# BD0006.net
KiCad netlist of a schematic drawn in EAGLE
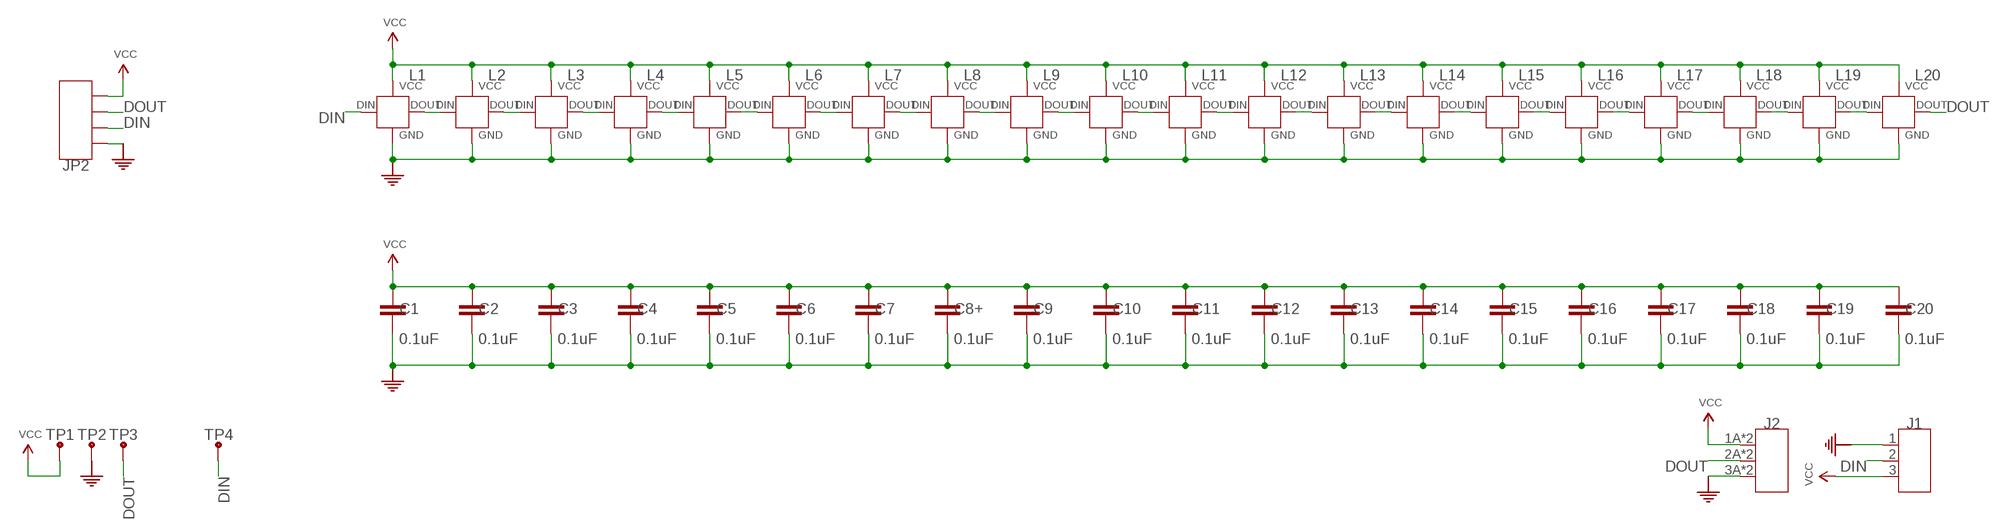
[diagram p0: schematic, sheet 1]

(export (version "E")
  (design (tool "Eeschema 10.0.6"))
  (components
    (comp (ref "C1")
      (value "0.1uF")
      (footprint "eagle-import:0402")
      (libsource (lib "eagle-import") (part "CAPACITOR-0402"))
    )
    (comp (ref "C2")
      (value "0.1uF")
      (footprint "eagle-import:0402")
      (libsource (lib "eagle-import") (part "CAPACITOR-0402"))
    )
    (comp (ref "C3")
      (value "0.1uF")
      (footprint "eagle-import:0402")
      (libsource (lib "eagle-import") (part "CAPACITOR-0402"))
    )
    (comp (ref "C4")
      (value "0.1uF")
      (footprint "eagle-import:0402")
      (libsource (lib "eagle-import") (part "CAPACITOR-0402"))
    )
    (comp (ref "C5")
      (value "0.1uF")
      (footprint "eagle-import:0402")
      (libsource (lib "eagle-import") (part "CAPACITOR-0402"))
    )
    (comp (ref "C6")
      (value "0.1uF")
      (footprint "eagle-import:0402")
      (libsource (lib "eagle-import") (part "CAPACITOR-0402"))
    )
    (comp (ref "C7")
      (value "0.1uF")
      (footprint "eagle-import:0402")
      (libsource (lib "eagle-import") (part "CAPACITOR-0402"))
    )
    (comp (ref "C8+")
      (value "0.1uF")
      (footprint "eagle-import:0402")
      (libsource (lib "eagle-import") (part "CAPACITOR-0402"))
    )
    (comp (ref "C9")
      (value "0.1uF")
      (footprint "eagle-import:0402")
      (libsource (lib "eagle-import") (part "CAPACITOR-0402"))
    )
    (comp (ref "C10")
      (value "0.1uF")
      (footprint "eagle-import:0402")
      (libsource (lib "eagle-import") (part "CAPACITOR-0402"))
    )
    (comp (ref "C11")
      (value "0.1uF")
      (footprint "eagle-import:0402")
      (libsource (lib "eagle-import") (part "CAPACITOR-0402"))
    )
    (comp (ref "C12")
      (value "0.1uF")
      (footprint "eagle-import:0402")
      (libsource (lib "eagle-import") (part "CAPACITOR-0402"))
    )
    (comp (ref "C13")
      (value "0.1uF")
      (footprint "eagle-import:0402")
      (libsource (lib "eagle-import") (part "CAPACITOR-0402"))
    )
    (comp (ref "C14")
      (value "0.1uF")
      (footprint "eagle-import:0402")
      (libsource (lib "eagle-import") (part "CAPACITOR-0402"))
    )
    (comp (ref "C15")
      (value "0.1uF")
      (footprint "eagle-import:0402")
      (libsource (lib "eagle-import") (part "CAPACITOR-0402"))
    )
    (comp (ref "C16")
      (value "0.1uF")
      (footprint "eagle-import:0402")
      (libsource (lib "eagle-import") (part "CAPACITOR-0402"))
    )
    (comp (ref "C17")
      (value "0.1uF")
      (footprint "eagle-import:0402")
      (libsource (lib "eagle-import") (part "CAPACITOR-0402"))
    )
    (comp (ref "C18")
      (value "0.1uF")
      (footprint "eagle-import:0402")
      (libsource (lib "eagle-import") (part "CAPACITOR-0402"))
    )
    (comp (ref "C19")
      (value "0.1uF")
      (footprint "eagle-import:0402")
      (libsource (lib "eagle-import") (part "CAPACITOR-0402"))
    )
    (comp (ref "C20")
      (value "0.1uF")
      (footprint "eagle-import:0402")
      (libsource (lib "eagle-import") (part "CAPACITOR-0402"))
    )
    (comp (ref "J1")
      (value "HEADER_1X3MALE")
      (footprint "eagle-import:M3SMD_RIGHTANGLE")
      (libsource (lib "eagle-import") (part "HEADER_1X3MALE"))
    )
    (comp (ref "J2")
      (value "HEADER_1X3FEMALE")
      (footprint "eagle-import:F3SMD_RIGHTANGLE")
      (libsource (lib "eagle-import") (part "HEADER_1X3FEMALE"))
    )
    (comp (ref "JP2")
      (value "HEADER_1X4")
      (footprint "eagle-import:1X04-CLEANBIG")
      (libsource (lib "eagle-import") (part "HEADER_1X4"))
    )
    (comp (ref "L1")
      (value "WS2812B-B")
      (footprint "eagle-import:SK6812-B")
      (libsource (lib "eagle-import") (part "WS2812B-B"))
    )
    (comp (ref "L2")
      (value "WS2812B-B")
      (footprint "eagle-import:SK6812-B")
      (libsource (lib "eagle-import") (part "WS2812B-B"))
    )
    (comp (ref "L3")
      (value "WS2812B-B")
      (footprint "eagle-import:SK6812-B")
      (libsource (lib "eagle-import") (part "WS2812B-B"))
    )
    (comp (ref "L4")
      (value "WS2812B-B")
      (footprint "eagle-import:SK6812-B")
      (libsource (lib "eagle-import") (part "WS2812B-B"))
    )
    (comp (ref "L5")
      (value "WS2812B-B")
      (footprint "eagle-import:SK6812-B")
      (libsource (lib "eagle-import") (part "WS2812B-B"))
    )
    (comp (ref "L6")
      (value "WS2812B-B")
      (footprint "eagle-import:SK6812-B")
      (libsource (lib "eagle-import") (part "WS2812B-B"))
    )
    (comp (ref "L7")
      (value "WS2812B-B")
      (footprint "eagle-import:SK6812-B")
      (libsource (lib "eagle-import") (part "WS2812B-B"))
    )
    (comp (ref "L8")
      (value "WS2812B-B")
      (footprint "eagle-import:SK6812-B")
      (libsource (lib "eagle-import") (part "WS2812B-B"))
    )
    (comp (ref "L9")
      (value "WS2812B-B")
      (footprint "eagle-import:SK6812-B")
      (libsource (lib "eagle-import") (part "WS2812B-B"))
    )
    (comp (ref "L10")
      (value "WS2812B-B")
      (footprint "eagle-import:SK6812-B")
      (libsource (lib "eagle-import") (part "WS2812B-B"))
    )
    (comp (ref "L11")
      (value "WS2812B-B")
      (footprint "eagle-import:SK6812-B")
      (libsource (lib "eagle-import") (part "WS2812B-B"))
    )
    (comp (ref "L12")
      (value "WS2812B-B")
      (footprint "eagle-import:SK6812-B")
      (libsource (lib "eagle-import") (part "WS2812B-B"))
    )
    (comp (ref "L13")
      (value "WS2812B-B")
      (footprint "eagle-import:SK6812-B")
      (libsource (lib "eagle-import") (part "WS2812B-B"))
    )
    (comp (ref "L14")
      (value "WS2812B-B")
      (footprint "eagle-import:SK6812-B")
      (libsource (lib "eagle-import") (part "WS2812B-B"))
    )
    (comp (ref "L15")
      (value "WS2812B-B")
      (footprint "eagle-import:SK6812-B")
      (libsource (lib "eagle-import") (part "WS2812B-B"))
    )
    (comp (ref "L16")
      (value "WS2812B-B")
      (footprint "eagle-import:SK6812-B")
      (libsource (lib "eagle-import") (part "WS2812B-B"))
    )
    (comp (ref "L17")
      (value "WS2812B-B")
      (footprint "eagle-import:SK6812-B")
      (libsource (lib "eagle-import") (part "WS2812B-B"))
    )
    (comp (ref "L18")
      (value "WS2812B-B")
      (footprint "eagle-import:SK6812-B")
      (libsource (lib "eagle-import") (part "WS2812B-B"))
    )
    (comp (ref "L19")
      (value "WS2812B-B")
      (footprint "eagle-import:SK6812-B")
      (libsource (lib "eagle-import") (part "WS2812B-B"))
    )
    (comp (ref "L20")
      (value "WS2812B-B")
      (footprint "eagle-import:SK6812-B")
      (libsource (lib "eagle-import") (part "WS2812B-B"))
    )
    (comp (ref "TP1")
      (value "VCC")
      (footprint "eagle-import:TEST_POINT")
      (libsource (lib "eagle-import") (part "TEST_POINT"))
    )
    (comp (ref "TP2")
      (value "GND")
      (footprint "eagle-import:TEST_POINT")
      (libsource (lib "eagle-import") (part "TEST_POINT"))
    )
    (comp (ref "TP3")
      (value "DOUT")
      (footprint "eagle-import:TEST_POINT")
      (libsource (lib "eagle-import") (part "TEST_POINT"))
    )
    (comp (ref "TP4")
      (value "DIN")
      (footprint "eagle-import:TEST_POINT")
      (libsource (lib "eagle-import") (part "TEST_POINT"))
    )
  )
  (nets
    (net (code "1") (name "/DIN") (class "Default")
      (node (ref "J1") (pin "2") (pinfunction "P$2_2") (pintype "bidirectional"))
      (node (ref "JP2") (pin "2") (pinfunction "P$2_2") (pintype "bidirectional"))
      (node (ref "L1") (pin "2") (pinfunction "DIN_2") (pintype "bidirectional"))
      (node (ref "TP4") (pin "P$1") (pinfunction "P$1_P$1") (pintype "input"))
    )
    (net (code "2") (name "/DOUT") (class "Default")
      (node (ref "J2") (pin "2A") (pinfunction "P$2_2A") (pintype "bidirectional"))
      (node (ref "J2") (pin "2B") (pinfunction "P$2_2B") (pintype "bidirectional"))
      (node (ref "JP2") (pin "3") (pinfunction "P$3_3") (pintype "bidirectional"))
      (node (ref "L20") (pin "4") (pinfunction "DOUT_4") (pintype "bidirectional"))
      (node (ref "TP3") (pin "P$1") (pinfunction "P$1_P$1") (pintype "input"))
    )
    (net (code "3") (name "GND") (class "Default")
      (node (ref "C1") (pin "P$2") (pinfunction "2_P$2") (pintype "passive"))
      (node (ref "C10") (pin "P$2") (pinfunction "2_P$2") (pintype "passive"))
      (node (ref "C11") (pin "P$2") (pinfunction "2_P$2") (pintype "passive"))
      (node (ref "C12") (pin "P$2") (pinfunction "2_P$2") (pintype "passive"))
      (node (ref "C13") (pin "P$2") (pinfunction "2_P$2") (pintype "passive"))
      (node (ref "C14") (pin "P$2") (pinfunction "2_P$2") (pintype "passive"))
      (node (ref "C15") (pin "P$2") (pinfunction "2_P$2") (pintype "passive"))
      (node (ref "C16") (pin "P$2") (pinfunction "2_P$2") (pintype "passive"))
      (node (ref "C17") (pin "P$2") (pinfunction "2_P$2") (pintype "passive"))
      (node (ref "C18") (pin "P$2") (pinfunction "2_P$2") (pintype "passive"))
      (node (ref "C19") (pin "P$2") (pinfunction "2_P$2") (pintype "passive"))
      (node (ref "C2") (pin "P$2") (pinfunction "2_P$2") (pintype "passive"))
      (node (ref "C20") (pin "P$2") (pinfunction "2_P$2") (pintype "passive"))
      (node (ref "C3") (pin "P$2") (pinfunction "2_P$2") (pintype "passive"))
      (node (ref "C4") (pin "P$2") (pinfunction "2_P$2") (pintype "passive"))
      (node (ref "C5") (pin "P$2") (pinfunction "2_P$2") (pintype "passive"))
      (node (ref "C6") (pin "P$2") (pinfunction "2_P$2") (pintype "passive"))
      (node (ref "C7") (pin "P$2") (pinfunction "2_P$2") (pintype "passive"))
      (node (ref "C8+") (pin "P$2") (pinfunction "2_P$2") (pintype "passive"))
      (node (ref "C9") (pin "P$2") (pinfunction "2_P$2") (pintype "passive"))
      (node (ref "J1") (pin "1") (pinfunction "P$1_1") (pintype "bidirectional"))
      (node (ref "J2") (pin "3A") (pinfunction "P$3_3A") (pintype "bidirectional"))
      (node (ref "J2") (pin "3B") (pinfunction "P$3_3B") (pintype "bidirectional"))
      (node (ref "JP2") (pin "1") (pinfunction "P$1_1") (pintype "bidirectional"))
      (node (ref "L1") (pin "1") (pinfunction "VSS_1") (pintype "bidirectional"))
      (node (ref "L10") (pin "1") (pinfunction "VSS_1") (pintype "bidirectional"))
      (node (ref "L11") (pin "1") (pinfunction "VSS_1") (pintype "bidirectional"))
      (node (ref "L12") (pin "1") (pinfunction "VSS_1") (pintype "bidirectional"))
      (node (ref "L13") (pin "1") (pinfunction "VSS_1") (pintype "bidirectional"))
      (node (ref "L14") (pin "1") (pinfunction "VSS_1") (pintype "bidirectional"))
      (node (ref "L15") (pin "1") (pinfunction "VSS_1") (pintype "bidirectional"))
      (node (ref "L16") (pin "1") (pinfunction "VSS_1") (pintype "bidirectional"))
      (node (ref "L17") (pin "1") (pinfunction "VSS_1") (pintype "bidirectional"))
      (node (ref "L18") (pin "1") (pinfunction "VSS_1") (pintype "bidirectional"))
      (node (ref "L19") (pin "1") (pinfunction "VSS_1") (pintype "bidirectional"))
      (node (ref "L2") (pin "1") (pinfunction "VSS_1") (pintype "bidirectional"))
      (node (ref "L20") (pin "1") (pinfunction "VSS_1") (pintype "bidirectional"))
      (node (ref "L3") (pin "1") (pinfunction "VSS_1") (pintype "bidirectional"))
      (node (ref "L4") (pin "1") (pinfunction "VSS_1") (pintype "bidirectional"))
      (node (ref "L5") (pin "1") (pinfunction "VSS_1") (pintype "bidirectional"))
      (node (ref "L6") (pin "1") (pinfunction "VSS_1") (pintype "bidirectional"))
      (node (ref "L7") (pin "1") (pinfunction "VSS_1") (pintype "bidirectional"))
      (node (ref "L8") (pin "1") (pinfunction "VSS_1") (pintype "bidirectional"))
      (node (ref "L9") (pin "1") (pinfunction "VSS_1") (pintype "bidirectional"))
      (node (ref "TP2") (pin "P$1") (pinfunction "P$1_P$1") (pintype "input"))
    )
    (net (code "4") (name "Net-(L1-DOUT)") (class "Default")
      (node (ref "L1") (pin "4") (pinfunction "DOUT_4") (pintype "bidirectional"))
      (node (ref "L2") (pin "2") (pinfunction "DIN_2") (pintype "bidirectional"))
    )
    (net (code "5") (name "Net-(L2-DOUT)") (class "Default")
      (node (ref "L2") (pin "4") (pinfunction "DOUT_4") (pintype "bidirectional"))
      (node (ref "L3") (pin "2") (pinfunction "DIN_2") (pintype "bidirectional"))
    )
    (net (code "6") (name "Net-(L3-DOUT)") (class "Default")
      (node (ref "L3") (pin "4") (pinfunction "DOUT_4") (pintype "bidirectional"))
      (node (ref "L4") (pin "2") (pinfunction "DIN_2") (pintype "bidirectional"))
    )
    (net (code "7") (name "Net-(L4-DOUT)") (class "Default")
      (node (ref "L4") (pin "4") (pinfunction "DOUT_4") (pintype "bidirectional"))
      (node (ref "L5") (pin "2") (pinfunction "DIN_2") (pintype "bidirectional"))
    )
    (net (code "8") (name "Net-(L5-DOUT)") (class "Default")
      (node (ref "L5") (pin "4") (pinfunction "DOUT_4") (pintype "bidirectional"))
      (node (ref "L6") (pin "2") (pinfunction "DIN_2") (pintype "bidirectional"))
    )
    (net (code "9") (name "Net-(L6-DOUT)") (class "Default")
      (node (ref "L6") (pin "4") (pinfunction "DOUT_4") (pintype "bidirectional"))
      (node (ref "L7") (pin "2") (pinfunction "DIN_2") (pintype "bidirectional"))
    )
    (net (code "10") (name "Net-(L7-DOUT)") (class "Default")
      (node (ref "L7") (pin "4") (pinfunction "DOUT_4") (pintype "bidirectional"))
      (node (ref "L8") (pin "2") (pinfunction "DIN_2") (pintype "bidirectional"))
    )
    (net (code "11") (name "Net-(L8-DOUT)") (class "Default")
      (node (ref "L8") (pin "4") (pinfunction "DOUT_4") (pintype "bidirectional"))
      (node (ref "L9") (pin "2") (pinfunction "DIN_2") (pintype "bidirectional"))
    )
    (net (code "12") (name "Net-(L10-DIN)") (class "Default")
      (node (ref "L10") (pin "2") (pinfunction "DIN_2") (pintype "bidirectional"))
      (node (ref "L9") (pin "4") (pinfunction "DOUT_4") (pintype "bidirectional"))
    )
    (net (code "13") (name "Net-(L10-DOUT)") (class "Default")
      (node (ref "L10") (pin "4") (pinfunction "DOUT_4") (pintype "bidirectional"))
      (node (ref "L11") (pin "2") (pinfunction "DIN_2") (pintype "bidirectional"))
    )
    (net (code "14") (name "Net-(L11-DOUT)") (class "Default")
      (node (ref "L11") (pin "4") (pinfunction "DOUT_4") (pintype "bidirectional"))
      (node (ref "L12") (pin "2") (pinfunction "DIN_2") (pintype "bidirectional"))
    )
    (net (code "15") (name "Net-(L12-DOUT)") (class "Default")
      (node (ref "L12") (pin "4") (pinfunction "DOUT_4") (pintype "bidirectional"))
      (node (ref "L13") (pin "2") (pinfunction "DIN_2") (pintype "bidirectional"))
    )
    (net (code "16") (name "Net-(L13-DOUT)") (class "Default")
      (node (ref "L13") (pin "4") (pinfunction "DOUT_4") (pintype "bidirectional"))
      (node (ref "L14") (pin "2") (pinfunction "DIN_2") (pintype "bidirectional"))
    )
    (net (code "17") (name "Net-(L14-DOUT)") (class "Default")
      (node (ref "L14") (pin "4") (pinfunction "DOUT_4") (pintype "bidirectional"))
      (node (ref "L15") (pin "2") (pinfunction "DIN_2") (pintype "bidirectional"))
    )
    (net (code "18") (name "Net-(L15-DOUT)") (class "Default")
      (node (ref "L15") (pin "4") (pinfunction "DOUT_4") (pintype "bidirectional"))
      (node (ref "L16") (pin "2") (pinfunction "DIN_2") (pintype "bidirectional"))
    )
    (net (code "19") (name "Net-(L16-DOUT)") (class "Default")
      (node (ref "L16") (pin "4") (pinfunction "DOUT_4") (pintype "bidirectional"))
      (node (ref "L17") (pin "2") (pinfunction "DIN_2") (pintype "bidirectional"))
    )
    (net (code "20") (name "Net-(L17-DOUT)") (class "Default")
      (node (ref "L17") (pin "4") (pinfunction "DOUT_4") (pintype "bidirectional"))
      (node (ref "L18") (pin "2") (pinfunction "DIN_2") (pintype "bidirectional"))
    )
    (net (code "21") (name "Net-(L18-DOUT)") (class "Default")
      (node (ref "L18") (pin "4") (pinfunction "DOUT_4") (pintype "bidirectional"))
      (node (ref "L19") (pin "2") (pinfunction "DIN_2") (pintype "bidirectional"))
    )
    (net (code "22") (name "Net-(L19-DOUT)") (class "Default")
      (node (ref "L19") (pin "4") (pinfunction "DOUT_4") (pintype "bidirectional"))
      (node (ref "L20") (pin "2") (pinfunction "DIN_2") (pintype "bidirectional"))
    )
    (net (code "23") (name "VCC") (class "Default")
      (node (ref "C1") (pin "P$1") (pinfunction "1_P$1") (pintype "passive"))
      (node (ref "C10") (pin "P$1") (pinfunction "1_P$1") (pintype "passive"))
      (node (ref "C11") (pin "P$1") (pinfunction "1_P$1") (pintype "passive"))
      (node (ref "C12") (pin "P$1") (pinfunction "1_P$1") (pintype "passive"))
      (node (ref "C13") (pin "P$1") (pinfunction "1_P$1") (pintype "passive"))
      (node (ref "C14") (pin "P$1") (pinfunction "1_P$1") (pintype "passive"))
      (node (ref "C15") (pin "P$1") (pinfunction "1_P$1") (pintype "passive"))
      (node (ref "C16") (pin "P$1") (pinfunction "1_P$1") (pintype "passive"))
      (node (ref "C17") (pin "P$1") (pinfunction "1_P$1") (pintype "passive"))
      (node (ref "C18") (pin "P$1") (pinfunction "1_P$1") (pintype "passive"))
      (node (ref "C19") (pin "P$1") (pinfunction "1_P$1") (pintype "passive"))
      (node (ref "C2") (pin "P$1") (pinfunction "1_P$1") (pintype "passive"))
      (node (ref "C20") (pin "P$1") (pinfunction "1_P$1") (pintype "passive"))
      (node (ref "C3") (pin "P$1") (pinfunction "1_P$1") (pintype "passive"))
      (node (ref "C4") (pin "P$1") (pinfunction "1_P$1") (pintype "passive"))
      (node (ref "C5") (pin "P$1") (pinfunction "1_P$1") (pintype "passive"))
      (node (ref "C6") (pin "P$1") (pinfunction "1_P$1") (pintype "passive"))
      (node (ref "C7") (pin "P$1") (pinfunction "1_P$1") (pintype "passive"))
      (node (ref "C8+") (pin "P$1") (pinfunction "1_P$1") (pintype "passive"))
      (node (ref "C9") (pin "P$1") (pinfunction "1_P$1") (pintype "passive"))
      (node (ref "J1") (pin "3") (pinfunction "P$3_3") (pintype "bidirectional"))
      (node (ref "J2") (pin "1A") (pinfunction "P$1_1A") (pintype "bidirectional"))
      (node (ref "J2") (pin "1B") (pinfunction "P$1_1B") (pintype "bidirectional"))
      (node (ref "JP2") (pin "4") (pinfunction "P$4_4") (pintype "bidirectional"))
      (node (ref "L1") (pin "3") (pinfunction "VDD_3") (pintype "bidirectional"))
      (node (ref "L10") (pin "3") (pinfunction "VDD_3") (pintype "bidirectional"))
      (node (ref "L11") (pin "3") (pinfunction "VDD_3") (pintype "bidirectional"))
      (node (ref "L12") (pin "3") (pinfunction "VDD_3") (pintype "bidirectional"))
      (node (ref "L13") (pin "3") (pinfunction "VDD_3") (pintype "bidirectional"))
      (node (ref "L14") (pin "3") (pinfunction "VDD_3") (pintype "bidirectional"))
      (node (ref "L15") (pin "3") (pinfunction "VDD_3") (pintype "bidirectional"))
      (node (ref "L16") (pin "3") (pinfunction "VDD_3") (pintype "bidirectional"))
      (node (ref "L17") (pin "3") (pinfunction "VDD_3") (pintype "bidirectional"))
      (node (ref "L18") (pin "3") (pinfunction "VDD_3") (pintype "bidirectional"))
      (node (ref "L19") (pin "3") (pinfunction "VDD_3") (pintype "bidirectional"))
      (node (ref "L2") (pin "3") (pinfunction "VDD_3") (pintype "bidirectional"))
      (node (ref "L20") (pin "3") (pinfunction "VDD_3") (pintype "bidirectional"))
      (node (ref "L3") (pin "3") (pinfunction "VDD_3") (pintype "bidirectional"))
      (node (ref "L4") (pin "3") (pinfunction "VDD_3") (pintype "bidirectional"))
      (node (ref "L5") (pin "3") (pinfunction "VDD_3") (pintype "bidirectional"))
      (node (ref "L6") (pin "3") (pinfunction "VDD_3") (pintype "bidirectional"))
      (node (ref "L7") (pin "3") (pinfunction "VDD_3") (pintype "bidirectional"))
      (node (ref "L8") (pin "3") (pinfunction "VDD_3") (pintype "bidirectional"))
      (node (ref "L9") (pin "3") (pinfunction "VDD_3") (pintype "bidirectional"))
      (node (ref "TP1") (pin "P$1") (pinfunction "P$1_P$1") (pintype "input"))
    )
  )
)
